# opamps.net
KiCad netlist of a schematic drawn in Altium Designer
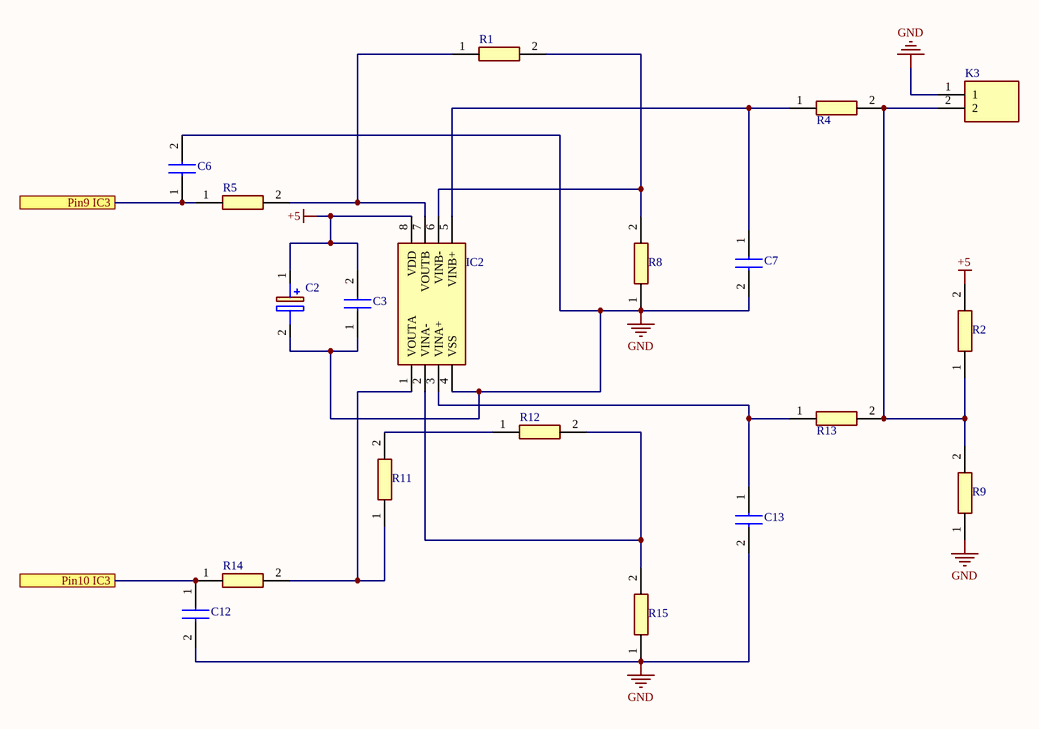
[diagram p0: opamps.SchDoc]

(export (version "E")
  (design (tool "Eeschema 10.0.6"))
  (components
    (comp (ref "C2")
      (value "860240672002")
      (footprint "SamacSys:CAPPRD200W52D500H1250")
      (description "Capacitor Polarised 10uf 50v stee 2mm 5x11mm")
      (libsource (lib "*") (part "860240672002"))
    )
    (comp (ref "C3")
      (value "885012207098")
      (footprint "SamacSys:CAPC2012X90N")
      (description "Capacitor, C3,C8,C9,C11,C14 100nf")
      (fields (field (name "MOUSER2 PART NUMBER") "710-885012207098"))
      (libsource (lib "*") (part "885012207098"))
    )
    (comp (ref "C6")
      (value "885012205067")
      (footprint "SamacSys:CAPC2012X90N")
      (description "Capacitor C6, C7, C12,C13")
      (libsource (lib "*") (part "885012205067"))
    )
    (comp (ref "C7")
      (value "885012205067")
      (footprint "SamacSys:CAPC2012X90N")
      (description "Capacitor C6, C7, C12,C13")
      (libsource (lib "*") (part "885012205067"))
    )
    (comp (ref "C12")
      (value "885012205067")
      (footprint "SamacSys:CAPC2012X90N")
      (description "Capacitor C6, C7, C12,C13")
      (libsource (lib "*") (part "885012205067"))
    )
    (comp (ref "C13")
      (value "885012205067")
      (footprint "SamacSys:CAPC2012X90N")
      (description "Capacitor C6, C7, C12,C13")
      (libsource (lib "*") (part "885012205067"))
    )
    (comp (ref "IC2")
      (value "MCP6002-E_P")
      (footprint "SamacSys:DIP781W56P254L950H533Q8N")
      (description "IC Dual Opamp")
      (fields
        (field (name "MOUSER2 PART NUMBER") "579-MCP6002-E/P")
        (field (name "MANUFACTURER_PART_NUMBER") "MCP6002-E/P")
      )
      (libsource (lib "*") (part "MCP6002-E_P"))
    )
    (comp (ref "K3")
      (value "691214110002")
      (footprint "SamacSys:691214110002")
      (description "Connector K3")
      (libsource (lib "SamacSys") (part "691214110002"))
    )
    (comp (ref "R1")
      (value "smd")
      (footprint "SamacSys:RESC2012X60N")
      (description "100k")
      (fields
        (field (name "MOUSER2 PART NUMBER") "71-CRCW08051M00JNEAC")
        (field (name "MANUFACTURER_PART_NUMBER") "CRCW08051M00JNEAC")
      )
      (libsource (lib "") (part "CRCW08051M00JNEAC_1"))
    )
    (comp (ref "R2")
      (value "smd")
      (footprint "SamacSys:RESC2012X60N")
      (description "1m")
      (fields
        (field (name "MOUSER2 PART NUMBER") "71-CRCW08051M00JNEAC")
        (field (name "MANUFACTURER_PART_NUMBER") "CRCW08051M00JNEAC")
      )
      (libsource (lib "SamacSys") (part "CRCW08051M00JNEAC"))
    )
    (comp (ref "R4")
      (value "smd")
      (footprint "SamacSys:RESC2012X60N")
      (description "100k")
      (fields
        (field (name "MOUSER2 PART NUMBER") "71-CRCW08051M00JNEAC")
        (field (name "MANUFACTURER_PART_NUMBER") "CRCW08051M00JNEAC")
      )
      (libsource (lib "") (part "CRCW08051M00JNEAC_1"))
    )
    (comp (ref "R5")
      (value "smd")
      (footprint "SamacSys:RESC2012X60N")
      (description "100k")
      (fields
        (field (name "MOUSER2 PART NUMBER") "71-CRCW08051M00JNEAC")
        (field (name "MANUFACTURER_PART_NUMBER") "CRCW08051M00JNEAC")
      )
      (libsource (lib "") (part "CRCW08051M00JNEAC_1"))
    )
    (comp (ref "R8")
      (value "smd")
      (footprint "SamacSys:RESC2012X60N")
      (description "100k")
      (fields
        (field (name "MOUSER2 PART NUMBER") "71-CRCW08051M00JNEAC")
        (field (name "MANUFACTURER_PART_NUMBER") "CRCW08051M00JNEAC")
      )
      (libsource (lib "SamacSys") (part "CRCW08051M00JNEAC"))
    )
    (comp (ref "R9")
      (value "smd")
      (footprint "SamacSys:RESC2012X60N")
      (description "10m")
      (fields
        (field (name "MOUSER2 PART NUMBER") "71-CRCW08051M00JNEAC")
        (field (name "MANUFACTURER_PART_NUMBER") "CRCW08051M00JNEAC")
      )
      (libsource (lib "SamacSys") (part "CRCW08051M00JNEAC"))
    )
    (comp (ref "R11")
      (value "smd")
      (footprint "SamacSys:RESC2012X60N")
      (description "18k")
      (fields
        (field (name "MOUSER2 PART NUMBER") "71-CRCW08051M00JNEAC")
        (field (name "MANUFACTURER_PART_NUMBER") "CRCW08051M00JNEAC")
      )
      (libsource (lib "SamacSys") (part "CRCW08051M00JNEAC"))
    )
    (comp (ref "R12")
      (value "smd")
      (footprint "SamacSys:RESC2012X60N")
      (description "18k")
      (fields
        (field (name "MOUSER2 PART NUMBER") "71-CRCW08051M00JNEAC")
        (field (name "MANUFACTURER_PART_NUMBER") "CRCW08051M00JNEAC")
      )
      (libsource (lib "") (part "CRCW08051M00JNEAC_1"))
    )
    (comp (ref "R13")
      (value "smd")
      (footprint "SamacSys:RESC2012X60N")
      (description "5k6")
      (fields
        (field (name "MOUSER2 PART NUMBER") "71-CRCW08051M00JNEAC")
        (field (name "MANUFACTURER_PART_NUMBER") "CRCW08051M00JNEAC")
      )
      (libsource (lib "") (part "CRCW08051M00JNEAC_1"))
    )
    (comp (ref "R14")
      (value "smd")
      (footprint "SamacSys:RESC2012X60N")
      (description "5k6")
      (fields
        (field (name "MOUSER2 PART NUMBER") "71-CRCW08051M00JNEAC")
        (field (name "MANUFACTURER_PART_NUMBER") "CRCW08051M00JNEAC")
      )
      (libsource (lib "") (part "CRCW08051M00JNEAC_1"))
    )
    (comp (ref "R15")
      (value "smd")
      (footprint "SamacSys:RESC2012X60N")
      (description "100ohm")
      (fields
        (field (name "MOUSER2 PART NUMBER") "71-CRCW08051M00JNEAC")
        (field (name "MANUFACTURER_PART_NUMBER") "CRCW08051M00JNEAC")
      )
      (libsource (lib "SamacSys") (part "CRCW08051M00JNEAC"))
    )
  )
  (nets
    (net (code "1") (name "+5") (class "Default")
      (node (ref "C2") (pin "1") (pinfunction "+_1") (pintype "passive"))
      (node (ref "C3") (pin "2") (pinfunction "2_2") (pintype "passive"))
      (node (ref "IC2") (pin "8") (pinfunction "VDD_8") (pintype "passive"))
      (node (ref "R2") (pin "2") (pinfunction "2_2") (pintype "passive"))
    )
    (net (code "2") (name "/Pin9 IC3") (class "Default")
      (node (ref "C6") (pin "1") (pinfunction "1_1") (pintype "passive"))
      (node (ref "R5") (pin "1") (pinfunction "1_1") (pintype "passive"))
    )
    (net (code "3") (name "/Pin10 IC3") (class "Default")
      (node (ref "C12") (pin "1") (pinfunction "1_1") (pintype "passive"))
      (node (ref "R14") (pin "1") (pinfunction "1_1") (pintype "passive"))
    )
    (net (code "4") (name "GND") (class "Default")
      (node (ref "C12") (pin "2") (pinfunction "2_2") (pintype "passive"))
      (node (ref "C13") (pin "2") (pinfunction "2_2") (pintype "passive"))
      (node (ref "C2") (pin "2") (pinfunction "-_2") (pintype "passive"))
      (node (ref "C3") (pin "1") (pinfunction "1_1") (pintype "passive"))
      (node (ref "C6") (pin "2") (pinfunction "2_2") (pintype "passive"))
      (node (ref "C7") (pin "2") (pinfunction "2_2") (pintype "passive"))
      (node (ref "IC2") (pin "4") (pinfunction "VSS_4") (pintype "passive"))
      (node (ref "K3") (pin "1") (pinfunction "1_1") (pintype "passive"))
      (node (ref "R15") (pin "1") (pinfunction "1_1") (pintype "passive"))
      (node (ref "R8") (pin "1") (pinfunction "1_1") (pintype "passive"))
      (node (ref "R9") (pin "1") (pinfunction "1_1") (pintype "passive"))
    )
    (net (code "5") (name "Net-(IC2-VINA+)") (class "Default")
      (node (ref "C13") (pin "1") (pinfunction "1_1") (pintype "passive"))
      (node (ref "IC2") (pin "3") (pinfunction "VINA+_3") (pintype "passive"))
      (node (ref "R13") (pin "1") (pinfunction "1_1") (pintype "passive"))
    )
    (net (code "6") (name "Net-(IC2-VINA-)") (class "Default")
      (node (ref "IC2") (pin "2") (pinfunction "VINA-_2") (pintype "passive"))
      (node (ref "R12") (pin "2") (pinfunction "2_2") (pintype "passive"))
      (node (ref "R15") (pin "2") (pinfunction "2_2") (pintype "passive"))
    )
    (net (code "7") (name "Net-(IC2-VINB+)") (class "Default")
      (node (ref "C7") (pin "1") (pinfunction "1_1") (pintype "passive"))
      (node (ref "IC2") (pin "5") (pinfunction "VINB+_5") (pintype "passive"))
      (node (ref "R4") (pin "1") (pinfunction "1_1") (pintype "passive"))
    )
    (net (code "8") (name "Net-(IC2-VINB-)") (class "Default")
      (node (ref "IC2") (pin "6") (pinfunction "VINB-_6") (pintype "passive"))
      (node (ref "R1") (pin "2") (pinfunction "2_2") (pintype "passive"))
      (node (ref "R8") (pin "2") (pinfunction "2_2") (pintype "passive"))
    )
    (net (code "9") (name "Net-(IC2-VOUTA)") (class "Default")
      (node (ref "IC2") (pin "1") (pinfunction "VOUTA_1") (pintype "passive"))
      (node (ref "R11") (pin "1") (pinfunction "1_1") (pintype "passive"))
      (node (ref "R14") (pin "2") (pinfunction "2_2") (pintype "passive"))
    )
    (net (code "10") (name "Net-(IC2-VOUTB)") (class "Default")
      (node (ref "IC2") (pin "7") (pinfunction "VOUTB_7") (pintype "passive"))
      (node (ref "R1") (pin "1") (pinfunction "1_1") (pintype "passive"))
      (node (ref "R5") (pin "2") (pinfunction "2_2") (pintype "passive"))
    )
    (net (code "11") (name "Net-(K3-Pad2)") (class "Default")
      (node (ref "K3") (pin "2") (pinfunction "2_2") (pintype "passive"))
      (node (ref "R13") (pin "2") (pinfunction "2_2") (pintype "passive"))
      (node (ref "R2") (pin "1") (pinfunction "1_1") (pintype "passive"))
      (node (ref "R4") (pin "2") (pinfunction "2_2") (pintype "passive"))
      (node (ref "R9") (pin "2") (pinfunction "2_2") (pintype "passive"))
    )
    (net (code "12") (name "Net-(R11-Pad2)") (class "Default")
      (node (ref "R11") (pin "2") (pinfunction "2_2") (pintype "passive"))
      (node (ref "R12") (pin "1") (pinfunction "1_1") (pintype "passive"))
    )
  )
)
